# Cinesense.net
KiCad netlist of a schematic drawn in EAGLE
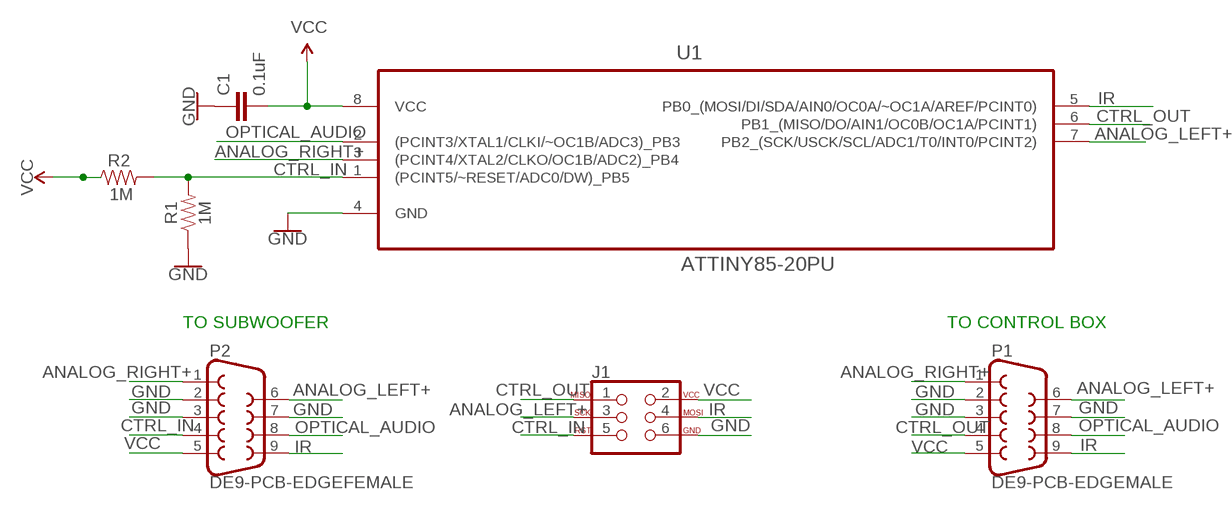
[diagram p0: schematic, sheet 1]

(export (version "E")
  (design (tool "Eeschema 10.0.6"))
  (components
    (comp (ref "C1")
      (value "0.1uF")
      (footprint "eagle-import:CAP-PTH-SMALL-KIT")
      (libsource (lib "eagle-import") (part "0.1UF-KIT-EZ-50V-20%"))
    )
    (comp (ref "J1")
      (value "AVR_SPI_PROG_3X2PTH")
      (footprint "eagle-import:2X3")
      (libsource (lib "eagle-import") (part "AVR_SPI_PROG_3X2PTH"))
    )
    (comp (ref "P1")
      (value "DE9-PCB-EDGEMALE")
      (footprint "eagle-import:DE9-EDGE-M")
      (libsource (lib "eagle-import") (part "DE9-PCB-EDGEMALE"))
    )
    (comp (ref "P2")
      (value "DE9-PCB-EDGEFEMALE")
      (footprint "eagle-import:DE9-EDGE-F")
      (libsource (lib "eagle-import") (part "DE9-PCB-EDGEFEMALE"))
    )
    (comp (ref "R1")
      (value "1M")
      (footprint "eagle-import:AXIAL-0.3")
      (libsource (lib "eagle-import") (part "RESISTORAXIAL-0.3"))
    )
    (comp (ref "R2")
      (value "1M")
      (footprint "eagle-import:AXIAL-0.3")
      (libsource (lib "eagle-import") (part "RESISTORAXIAL-0.3"))
    )
    (comp (ref "U1")
      (value "ATTINY85-20PU")
      (footprint "eagle-import:DIP254P762X533-8")
      (fields (field (name "MF") "Microchip"))
      (libsource (lib "eagle-import") (part "ATTINY85-20PU"))
    )
  )
  (nets
    (net (code "1") (name "/ANALOG_LEFT+") (class "Default")
      (node (ref "J1") (pin "3") (pinfunction "3_3") (pintype "passive"))
      (node (ref "P1") (pin "6") (pinfunction "6_6") (pintype "passive"))
      (node (ref "P2") (pin "6") (pinfunction "6_6") (pintype "passive"))
      (node (ref "U1") (pin "7") (pinfunction "PB2_(SCK/USCK/SCL/ADC1/T0/INT0/PCINT2)_7") (pintype "bidirectional"))
    )
    (net (code "2") (name "/ANALOG_RIGHT+") (class "Default")
      (node (ref "P1") (pin "1") (pinfunction "1_1") (pintype "passive"))
      (node (ref "P2") (pin "1") (pinfunction "1_1") (pintype "passive"))
      (node (ref "U1") (pin "3") (pinfunction "(PCINT4/XTAL2/CLKO/OC1B/ADC2)_PB4_3") (pintype "bidirectional"))
    )
    (net (code "3") (name "/CTRL_IN") (class "Default")
      (node (ref "J1") (pin "5") (pinfunction "5_5") (pintype "passive"))
      (node (ref "P2") (pin "4") (pinfunction "4_4") (pintype "passive"))
      (node (ref "R1") (pin "P$2") (pinfunction "2_P$2") (pintype "passive"))
      (node (ref "R2") (pin "P$2") (pinfunction "2_P$2") (pintype "passive"))
      (node (ref "U1") (pin "1") (pinfunction "(PCINT5/~{RESET/ADC0/DW})_PB5_1") (pintype "bidirectional"))
    )
    (net (code "4") (name "/CTRL_OUT") (class "Default")
      (node (ref "J1") (pin "1") (pinfunction "1_1") (pintype "passive"))
      (node (ref "P1") (pin "4") (pinfunction "4_4") (pintype "passive"))
      (node (ref "U1") (pin "6") (pinfunction "PB1_(MISO/DO/AIN1/OC0B/OC1A/PCINT1)_6") (pintype "bidirectional"))
    )
    (net (code "5") (name "/IR") (class "Default")
      (node (ref "J1") (pin "4") (pinfunction "4_4") (pintype "passive"))
      (node (ref "P1") (pin "9") (pinfunction "9_9") (pintype "passive"))
      (node (ref "P2") (pin "9") (pinfunction "9_9") (pintype "passive"))
      (node (ref "U1") (pin "5") (pinfunction "PB0_(MOSI/DI/SDA/AIN0/OC0A/~{OC1A/AREF/PCINT0})_5") (pintype "bidirectional"))
    )
    (net (code "6") (name "/OPTICAL_AUDIO") (class "Default")
      (node (ref "P1") (pin "8") (pinfunction "8_8") (pintype "passive"))
      (node (ref "P2") (pin "8") (pinfunction "8_8") (pintype "passive"))
      (node (ref "U1") (pin "2") (pinfunction "(PCINT3/XTAL1/CLKI/~{OC1B/ADC3})_PB3_2") (pintype "bidirectional"))
    )
    (net (code "7") (name "GND") (class "Default")
      (node (ref "C1") (pin "1") (pinfunction "1_1") (pintype "passive"))
      (node (ref "J1") (pin "6") (pinfunction "6_6") (pintype "passive"))
      (node (ref "P1") (pin "2") (pinfunction "2_2") (pintype "passive"))
      (node (ref "P1") (pin "3") (pinfunction "3_3") (pintype "passive"))
      (node (ref "P1") (pin "7") (pinfunction "7_7") (pintype "passive"))
      (node (ref "P2") (pin "2") (pinfunction "2_2") (pintype "passive"))
      (node (ref "P2") (pin "3") (pinfunction "3_3") (pintype "passive"))
      (node (ref "P2") (pin "7") (pinfunction "7_7") (pintype "passive"))
      (node (ref "R1") (pin "P$1") (pinfunction "1_P$1") (pintype "passive"))
      (node (ref "U1") (pin "4") (pinfunction "GND_4") (pintype "passive"))
    )
    (net (code "8") (name "VCC") (class "Default")
      (node (ref "C1") (pin "2") (pinfunction "2_2") (pintype "passive"))
      (node (ref "J1") (pin "2") (pinfunction "2_2") (pintype "passive"))
      (node (ref "P1") (pin "5") (pinfunction "5_5") (pintype "passive"))
      (node (ref "P2") (pin "5") (pinfunction "5_5") (pintype "passive"))
      (node (ref "R2") (pin "P$1") (pinfunction "1_P$1") (pintype "passive"))
      (node (ref "U1") (pin "8") (pinfunction "VCC_8") (pintype "power_in"))
    )
  )
)
